# Fiber_interlock.net
KiCad netlist of a schematic drawn in Altium Designer
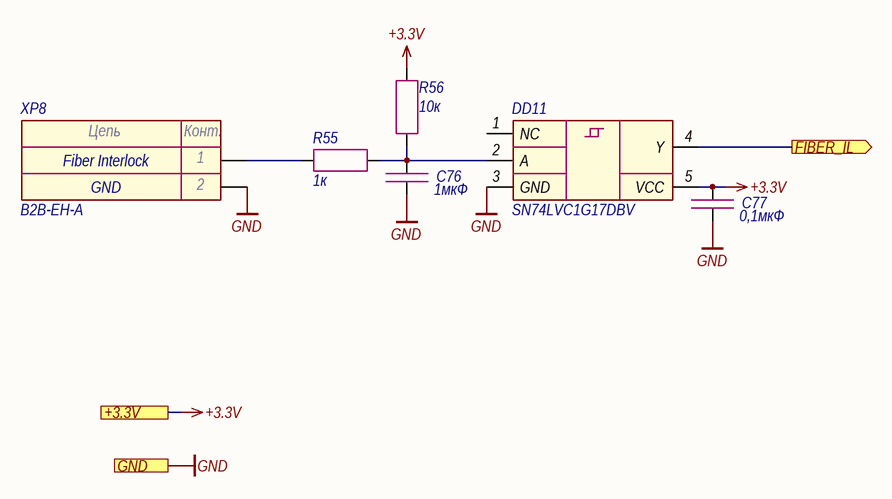
[diagram p0: Fiber_interlock.SchDoc]

(export (version "E")
  (design (tool "Eeschema 10.0.6"))
  (components
    (comp (ref "C76")
      (value "1мкФ")
      (footprint "Pcb_library:CAP_0603")
      (fields (field (name "MANUFACTURER") "Murata"))
      (libsource (lib "Schem_library") (part "Capacitor"))
    )
    (comp (ref "C77")
      (value "0,1мкФ")
      (footprint "Pcb_library:CAP_0603")
      (fields (field (name "MANUFACTURER") "Murata"))
      (libsource (lib "Schem_library") (part "Capacitor"))
    )
    (comp (ref "DD11")
      (value "SN74LVC1G17DBV")
      (footprint "Pcb_library:SOT-23-5")
      (fields (field (name "MANUFACTURER") "Texas Instruments"))
      (libsource (lib "Schem_library") (part "SN74LVC1G17"))
    )
    (comp (ref "R55")
      (value "1к")
      (footprint "Pcb_library:RES_0603")
      (fields (field (name "MANUFACTURER") "Yageo"))
      (libsource (lib "Schem_library") (part "Resistor"))
    )
    (comp (ref "R56")
      (value "10к")
      (footprint "Pcb_library:RES_0603")
      (fields (field (name "MANUFACTURER") "Yageo"))
      (libsource (lib "Schem_library") (part "Resistor"))
    )
    (comp (ref "XP8")
      (value "B2B-EH-A")
      (footprint "Pcb_library:B2B-EH-A")
      (fields (field (name "MANUFACTURER") "JST"))
      (libsource (lib "Schem_library") (part "Connector-2"))
    )
  )
  (nets
    (net (code "1") (name "+3.3V") (class "Default")
      (node (ref "C77") (pin "1") (pinfunction "1_1") (pintype "passive"))
      (node (ref "DD11") (pin "5") (pinfunction "VCC_5") (pintype "passive"))
      (node (ref "R56") (pin "2") (pinfunction "2_2") (pintype "passive"))
    )
    (net (code "2") (name "/FIBER_IL") (class "Default")
      (node (ref "DD11") (pin "4") (pinfunction "Y_4") (pintype "passive"))
    )
    (net (code "3") (name "GND") (class "Default")
      (node (ref "C76") (pin "2") (pinfunction "2_2") (pintype "passive"))
      (node (ref "C77") (pin "2") (pinfunction "2_2") (pintype "passive"))
      (node (ref "DD11") (pin "3") (pinfunction "GND_3") (pintype "passive"))
      (node (ref "XP8") (pin "2") (pintype "passive"))
    )
    (net (code "4") (name "Net-(DD11-A)") (class "Default")
      (node (ref "C76") (pin "1") (pinfunction "1_1") (pintype "passive"))
      (node (ref "DD11") (pin "2") (pinfunction "A_2") (pintype "passive"))
      (node (ref "R55") (pin "2") (pinfunction "2_2") (pintype "passive"))
      (node (ref "R56") (pin "1") (pinfunction "1_1") (pintype "passive"))
    )
    (net (code "5") (name "Net-(R55-Pad1)") (class "Default")
      (node (ref "R55") (pin "1") (pinfunction "1_1") (pintype "passive"))
      (node (ref "XP8") (pin "1") (pintype "passive"))
    )
    (net (code "6") (name "unconnected-(DD11-NC-Pad1)") (class "Default")
      (node (ref "DD11") (pin "1") (pinfunction "NC_1") (pintype "passive"))
    )
  )
)
